# sd-card.net
KiCad netlist of a schematic drawn in Altium Designer
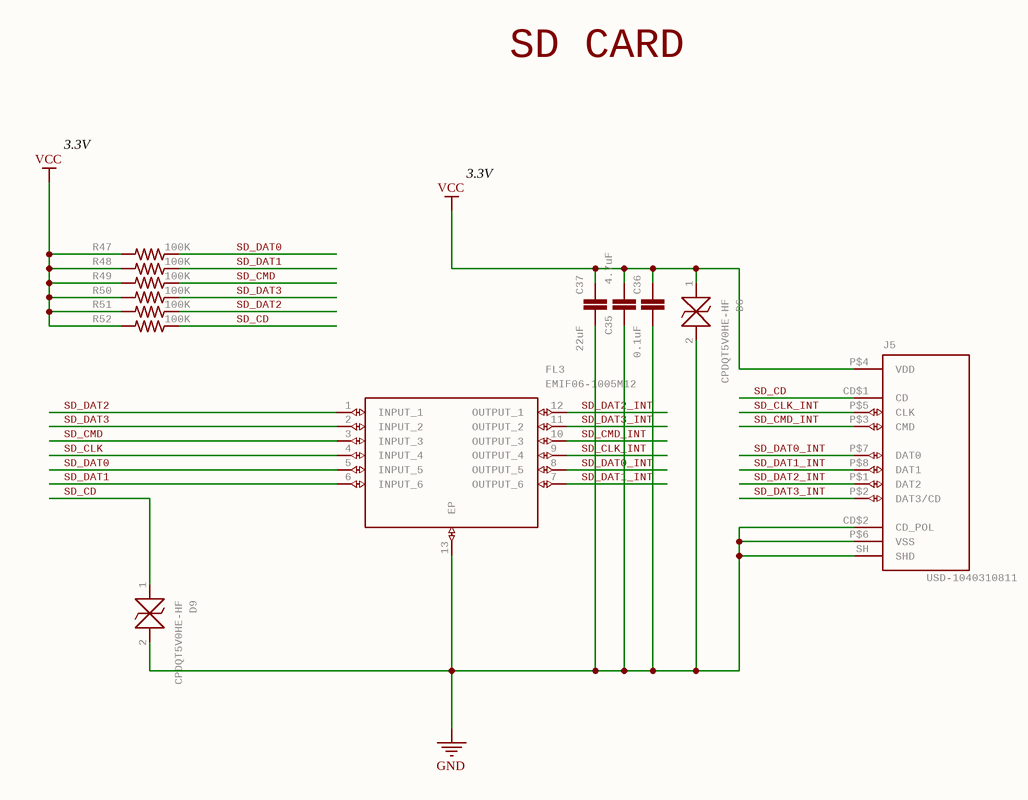
[diagram p0: sd-card.SchDoc]

(export (version "E")
  (design (tool "Eeschema 10.0.6"))
  (components
    (comp (ref "C35")
      (value "4.7uF")
      (footprint "0402-CAP")
      (description "CapacitorStandard 0603 ceramic capacitor, and 0.1\" leaded capacitor.")
      (fields (field (name "MPN") "JMK105BBJ475MV-F") (field (name "LIBRARYNAME") "sfe"))
      (libsource (lib "rt10") (part "CAP0402-CAP"))
    )
    (comp (ref "C36")
      (value "0.1uF")
      (footprint "0402-CAP")
      (description "CAPACITOR, European symbol")
      (fields (field (name "MPN") "C0402C104Z4VAC"))
      (libsource (lib "rt10") (part "C-EUC0201"))
    )
    (comp (ref "C37")
      (value "22uF")
      (footprint "0805")
      (fields (field (name "MPN") "CL21A226MQQNNNE"))
      (libsource (lib "rt10") (part "22UF-0805-6.3V-20%"))
    )
    (comp (ref "D6")
      (value "CPDQT5V0HE-HF")
      (footprint "CPDQT5V0HEHF")
      (description "ESD Suppressors / TVS Diodes DIODE ESD 5VWM 65W 0402/SOD-923F   Source:  Datasheet")
      (fields (field (name "MOUSER_PART_NUMBER") "MOUSER_PART_NUMBER"))
      (libsource (lib "rt10") (part "CPDQT5V0HE-HF"))
    )
    (comp (ref "D9")
      (value "CPDQT5V0HE-HF")
      (footprint "CPDQT5V0HEHF")
      (description "ESD Suppressors / TVS Diodes DIODE ESD 5VWM 65W 0402/SOD-923F   Source:  Datasheet")
      (fields (field (name "MOUSER_PART_NUMBER") "MOUSER_PART_NUMBER"))
      (libsource (lib "rt10") (part "CPDQT5V0HE-HF"))
    )
    (comp (ref "FL3")
      (value "EMIF06-1005M12")
      (footprint "SON40P150X250X65-13N")
      (description "EMI Filter Circuits 6lin lw cpcitnc EMI 45pF -35db @ 900MHz   Source:  Datasheet")
      (fields (field (name "MOUSER_PART_NUMBER") "511-EMIF06-1005M12"))
      (libsource (lib "rt10") (part "EMIF06-1005M12"))
    )
    (comp (ref "J5")
      (value "USD-1040310811")
      (footprint "1040310811")
      (description "uSD Slot")
      (fields (field (name "MPN") "104031-0811"))
      (libsource (lib "rt10") (part "USD-1040310811"))
    )
    (comp (ref "R47")
      (value "100K")
      (footprint "0402-RES")
      (description "ResistorBasic schematic elements and footprints for 0603, 1206, and PTH resistors.")
      (fields (field (name "MPN") "AC0402FR-07100KL") (field (name "LIBRARYNAME") "sfe"))
      (libsource (lib "rt10") (part "RESISTOR0402-RES"))
    )
    (comp (ref "R48")
      (value "100K")
      (footprint "0402-RES")
      (description "ResistorBasic schematic elements and footprints for 0603, 1206, and PTH resistors.")
      (fields (field (name "MPN") "AC0402FR-07100KL") (field (name "LIBRARYNAME") "sfe"))
      (libsource (lib "rt10") (part "RESISTOR0402-RES"))
    )
    (comp (ref "R49")
      (value "100K")
      (footprint "0402-RES")
      (description "ResistorBasic schematic elements and footprints for 0603, 1206, and PTH resistors.")
      (fields (field (name "MPN") "AC0402FR-07100KL") (field (name "LIBRARYNAME") "sfe"))
      (libsource (lib "rt10") (part "RESISTOR0402-RES"))
    )
    (comp (ref "R50")
      (value "100K")
      (footprint "0402-RES")
      (description "ResistorBasic schematic elements and footprints for 0603, 1206, and PTH resistors.")
      (fields (field (name "MPN") "AC0402FR-07100KL") (field (name "LIBRARYNAME") "sfe"))
      (libsource (lib "rt10") (part "RESISTOR0402-RES"))
    )
    (comp (ref "R51")
      (value "100K")
      (footprint "0402-RES")
      (description "ResistorBasic schematic elements and footprints for 0603, 1206, and PTH resistors.")
      (fields (field (name "MPN") "AC0402FR-07100KL") (field (name "LIBRARYNAME") "sfe"))
      (libsource (lib "rt10") (part "RESISTOR0402-RES"))
    )
    (comp (ref "R52")
      (value "100K")
      (footprint "0402-RES")
      (description "ResistorBasic schematic elements and footprints for 0603, 1206, and PTH resistors.")
      (fields (field (name "MPN") "AC0402FR-07100KL") (field (name "LIBRARYNAME") "sfe"))
      (libsource (lib "rt10") (part "RESISTOR0402-RES"))
    )
  )
  (nets
    (net (code "1") (name "/SD_CD") (class "Default")
      (node (ref "D9") (pin "1") (pinfunction "1_1") (pintype "bidirectional"))
      (node (ref "J5") (pin "CD$1") (pinfunction "CD_CD$1") (pintype "power_in"))
      (node (ref "R52") (pin "1") (pinfunction "1_1") (pintype "passive"))
    )
    (net (code "2") (name "/SD_CLK") (class "Default")
      (node (ref "FL3") (pin "4") (pinfunction "INPUT_4_4") (pintype "bidirectional"))
    )
    (net (code "3") (name "/SD_CLK_INT") (class "Default")
      (node (ref "FL3") (pin "9") (pinfunction "OUTPUT_4_9") (pintype "bidirectional"))
      (node (ref "J5") (pin "P$5") (pinfunction "CLK_P$5") (pintype "bidirectional"))
    )
    (net (code "4") (name "/SD_CMD") (class "Default")
      (node (ref "FL3") (pin "3") (pinfunction "INPUT_3_3") (pintype "bidirectional"))
      (node (ref "R49") (pin "1") (pinfunction "1_1") (pintype "passive"))
    )
    (net (code "5") (name "/SD_CMD_INT") (class "Default")
      (node (ref "FL3") (pin "10") (pinfunction "OUTPUT_3_10") (pintype "bidirectional"))
      (node (ref "J5") (pin "P$3") (pinfunction "CMD_P$3") (pintype "bidirectional"))
    )
    (net (code "6") (name "/SD_DAT0") (class "Default")
      (node (ref "FL3") (pin "5") (pinfunction "INPUT_5_5") (pintype "bidirectional"))
      (node (ref "R47") (pin "1") (pinfunction "1_1") (pintype "passive"))
    )
    (net (code "7") (name "/SD_DAT0_INT") (class "Default")
      (node (ref "FL3") (pin "8") (pinfunction "OUTPUT_5_8") (pintype "bidirectional"))
      (node (ref "J5") (pin "P$7") (pinfunction "DAT0_P$7") (pintype "bidirectional"))
    )
    (net (code "8") (name "/SD_DAT1") (class "Default")
      (node (ref "FL3") (pin "6") (pinfunction "INPUT_6_6") (pintype "bidirectional"))
      (node (ref "R48") (pin "1") (pinfunction "1_1") (pintype "passive"))
    )
    (net (code "9") (name "/SD_DAT1_INT") (class "Default")
      (node (ref "FL3") (pin "7") (pinfunction "OUTPUT_6_7") (pintype "bidirectional"))
      (node (ref "J5") (pin "P$8") (pinfunction "DAT1_P$8") (pintype "bidirectional"))
    )
    (net (code "10") (name "/SD_DAT2") (class "Default")
      (node (ref "FL3") (pin "1") (pinfunction "INPUT_1_1") (pintype "bidirectional"))
      (node (ref "R51") (pin "1") (pinfunction "1_1") (pintype "passive"))
    )
    (net (code "11") (name "/SD_DAT2_INT") (class "Default")
      (node (ref "FL3") (pin "12") (pinfunction "OUTPUT_1_12") (pintype "bidirectional"))
      (node (ref "J5") (pin "P$1") (pinfunction "DAT2_P$1") (pintype "bidirectional"))
    )
    (net (code "12") (name "/SD_DAT3") (class "Default")
      (node (ref "FL3") (pin "2") (pinfunction "INPUT_2_2") (pintype "bidirectional"))
      (node (ref "R50") (pin "1") (pinfunction "1_1") (pintype "passive"))
    )
    (net (code "13") (name "/SD_DAT3_INT") (class "Default")
      (node (ref "FL3") (pin "11") (pinfunction "OUTPUT_2_11") (pintype "bidirectional"))
      (node (ref "J5") (pin "P$2") (pinfunction "DAT3/CD_P$2") (pintype "bidirectional"))
    )
    (net (code "14") (name "GND") (class "Default")
      (node (ref "C35") (pin "1") (pinfunction "1_1") (pintype "passive"))
      (node (ref "C36") (pin "2") (pinfunction "2_2") (pintype "passive"))
      (node (ref "C37") (pin "2") (pinfunction "2_2") (pintype "passive"))
      (node (ref "D6") (pin "2") (pinfunction "2_2") (pintype "bidirectional"))
      (node (ref "D9") (pin "2") (pinfunction "2_2") (pintype "bidirectional"))
      (node (ref "FL3") (pin "13") (pinfunction "EP_13") (pintype "bidirectional"))
      (node (ref "J5") (pin "CD$2") (pinfunction "CD_POL_CD$2") (pintype "power_in"))
      (node (ref "J5") (pin "P$6") (pinfunction "VSS_P$6") (pintype "power_in"))
      (node (ref "J5") (pin "SH") (pinfunction "SHD_SH") (pintype "power_in"))
    )
    (net (code "15") (name "VCC") (class "Default")
      (node (ref "C35") (pin "2") (pinfunction "2_2") (pintype "passive"))
      (node (ref "C36") (pin "1") (pinfunction "1_1") (pintype "passive"))
      (node (ref "C37") (pin "1") (pinfunction "1_1") (pintype "passive"))
      (node (ref "D6") (pin "1") (pinfunction "1_1") (pintype "bidirectional"))
      (node (ref "J5") (pin "P$4") (pinfunction "VDD_P$4") (pintype "power_in"))
      (node (ref "R47") (pin "2") (pinfunction "2_2") (pintype "passive"))
      (node (ref "R48") (pin "2") (pinfunction "2_2") (pintype "passive"))
      (node (ref "R49") (pin "2") (pinfunction "2_2") (pintype "passive"))
      (node (ref "R50") (pin "2") (pinfunction "2_2") (pintype "passive"))
      (node (ref "R51") (pin "2") (pinfunction "2_2") (pintype "passive"))
      (node (ref "R52") (pin "2") (pinfunction "2_2") (pintype "passive"))
    )
  )
)
